# LiDAR_Schematic.net
KiCad netlist of a schematic drawn in Altium Designer
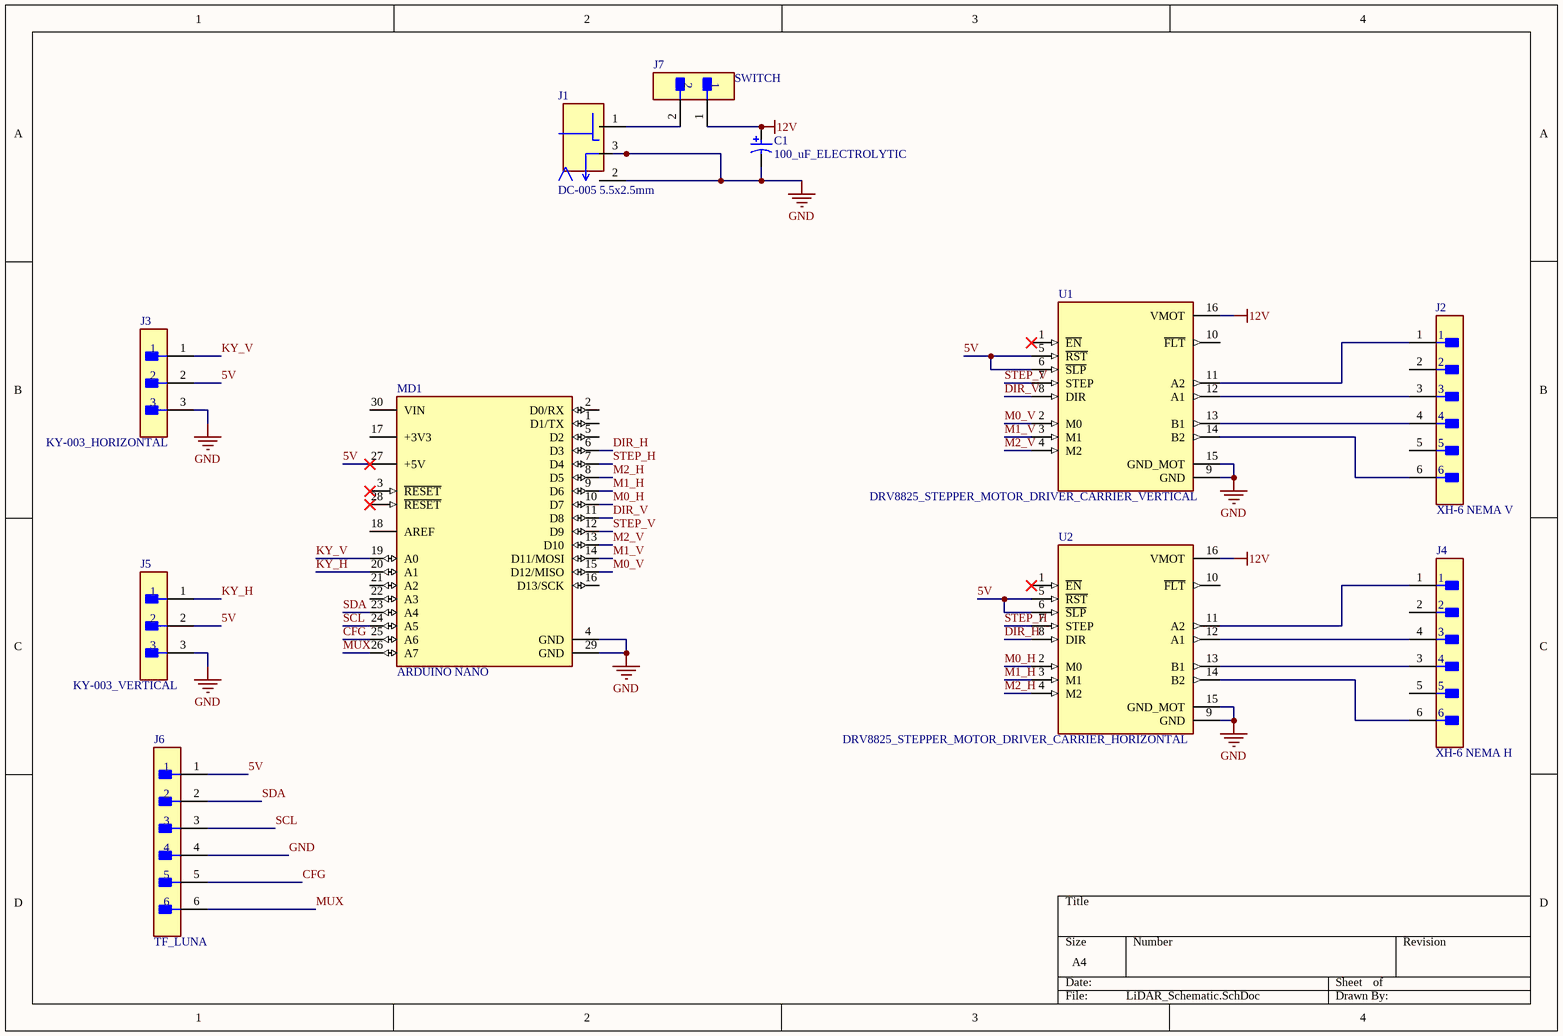
[diagram p0: LiDAR_Schematic.SchDoc]

(export (version "E")
  (design (tool "Eeschema 10.0.6"))
  (components
    (comp (ref "C1")
      (value "100_uF_ELECTROLYTIC")
      (footprint "CAPPR55-250-1120X630X1220")
      (fields (field (name "MANUFACTURER") "Panasonic"))
      (libsource (lib "Altium Content Vault") (part "CAP-P-2"))
    )
    (comp (ref "J1")
      (value "DC-005 5.5x2.5mm")
      (footprint "GCT_DCJ250-10-A-XX-X_REVA")
      (description "Power Barrel Connector Jack 2.55mm ID (0.100), 5.50mm OD (0.217) Through Hole, Right Angle")
      (fields (field (name "MP") "DCJ250-10-A-K1-K") (field (name "MF") "Global Connector Technology"))
      (libsource (lib "DCJ250-10-A-XX-X_REVA") (part "DCJ250-10-A-XX-X_REVA"))
    )
    (comp (ref "J2")
      (value "XH-6 NEMA V")
      (footprint "FP-B6B-XH-A_LF_SN-MFG")
      (description "CONN HEADER VERT 6POS 2.5MM")
      (libsource (lib "") (part "f2cb566baf1c37ab5a3b8e90bbeafd6_1"))
    )
    (comp (ref "J3")
      (value "KY-003_HORIZONTAL")
      (footprint "FP-87224-3-MFG")
      (description "CONN HEADER VERT 3POS 2.54MM")
      (libsource (lib "Altium Content Vault") (part "0d3f023dd272f625e17a2be33dea85f"))
    )
    (comp (ref "J4")
      (value "XH-6 NEMA H")
      (footprint "FP-B6B-XH-A_LF_SN-MFG")
      (description "CONN HEADER VERT 6POS 2.5MM")
      (libsource (lib "Altium Content Vault") (part "f2cb566baf1c37ab5a3b8e90bbeafd6"))
    )
    (comp (ref "J5")
      (value "KY-003_VERTICAL")
      (footprint "FP-87224-3-MFG")
      (description "CONN HEADER VERT 3POS 2.54MM")
      (libsource (lib "Altium Content Vault") (part "0d3f023dd272f625e17a2be33dea85f"))
    )
    (comp (ref "J6")
      (value "TF_LUNA")
      (footprint "FP-22-28-4060-MFG")
      (description "CONN HEADER VERT 6POS 2.54MM")
      (libsource (lib "") (part "f2cb566baf1c37ab5a3b8e90bbeafd6_2"))
    )
    (comp (ref "J7")
      (value "SWITCH")
      (footprint "FP-TSW-102-07-S-S-MFG")
      (description "CONN HEADER VERT 2POS 2.54MM")
      (libsource (lib "Altium Content Vault") (part "3bc925449376181038e59eaffc5286c"))
    )
    (comp (ref "MD1")
      (value "ARDUINO NANO")
      (footprint "FP-A000005-MFG")
      (description "ARDUINO NANO ATMEGA328 EVAL BRD")
      (libsource (lib "Altium Content Vault") (part "d190c066e99afd1c6882cf92e11b2cc"))
    )
    (comp (ref "U1")
      (value "DRV8825_STEPPER_MOTOR_DRIVER_CARRIER_VERTICAL")
      (footprint "IC_DRV8825_STEPPER_MOTOR_DRIVER_CARRIER")
      (description "Stepper motor controler; IC: DRV8825; 1.5A; Uin mot: 8.2Ã·45V")
      (fields (field (name "MP") "DRV8825_STEPPER_MOTOR_DRIVER_CARRIER"))
      (libsource (lib "DRV8825_STEPPER_MOTOR_DRIVER_CARRIER") (part "DRV8825_STEPPER_MOTOR_DRIVER_CARRIER"))
    )
    (comp (ref "U2")
      (value "DRV8825_STEPPER_MOTOR_DRIVER_CARRIER_HORIZONTAL")
      (footprint "IC_DRV8825_STEPPER_MOTOR_DRIVER_CARRIER")
      (description "Stepper motor controler; IC: DRV8825; 1.5A; Uin mot: 8.2Ã·45V")
      (fields (field (name "MP") "DRV8825_STEPPER_MOTOR_DRIVER_CARRIER"))
      (libsource (lib "DRV8825_STEPPER_MOTOR_DRIVER_CARRIER") (part "DRV8825_STEPPER_MOTOR_DRIVER_CARRIER"))
    )
  )
  (nets
    (net (code "1") (name "/5V") (class "Default")
      (node (ref "J3") (pin "2") (pinfunction "2_2") (pintype "passive"))
      (node (ref "J5") (pin "2") (pinfunction "2_2") (pintype "passive"))
      (node (ref "J6") (pin "1") (pinfunction "1_1") (pintype "passive"))
      (node (ref "MD1") (pin "27") (pinfunction "+5V_27") (pintype "power_in"))
      (node (ref "U1") (pin "5") (pinfunction "~{RST}_5") (pintype "input"))
      (node (ref "U1") (pin "6") (pinfunction "~{SLP}_6") (pintype "input"))
      (node (ref "U2") (pin "5") (pinfunction "~{RST}_5") (pintype "input"))
      (node (ref "U2") (pin "6") (pinfunction "~{SLP}_6") (pintype "input"))
    )
    (net (code "2") (name "/CFG") (class "Default")
      (node (ref "J6") (pin "5") (pinfunction "5_5") (pintype "passive"))
      (node (ref "MD1") (pin "25") (pinfunction "A6_25") (pintype "bidirectional"))
    )
    (net (code "3") (name "/DIR_H") (class "Default")
      (node (ref "MD1") (pin "6") (pinfunction "D3_6") (pintype "bidirectional"))
      (node (ref "U2") (pin "8") (pinfunction "DIR_8") (pintype "input"))
    )
    (net (code "4") (name "/DIR_V") (class "Default")
      (node (ref "MD1") (pin "11") (pinfunction "D8_11") (pintype "bidirectional"))
      (node (ref "U1") (pin "8") (pinfunction "DIR_8") (pintype "input"))
    )
    (net (code "5") (name "/KY_H") (class "Default")
      (node (ref "J5") (pin "1") (pinfunction "1_1") (pintype "passive"))
      (node (ref "MD1") (pin "20") (pinfunction "A1_20") (pintype "bidirectional"))
    )
    (net (code "6") (name "/KY_V") (class "Default")
      (node (ref "J3") (pin "1") (pinfunction "1_1") (pintype "passive"))
      (node (ref "MD1") (pin "19") (pinfunction "A0_19") (pintype "bidirectional"))
    )
    (net (code "7") (name "/M0_H") (class "Default")
      (node (ref "MD1") (pin "10") (pinfunction "D7_10") (pintype "bidirectional"))
      (node (ref "U2") (pin "2") (pinfunction "M0_2") (pintype "input"))
    )
    (net (code "8") (name "/M0_V") (class "Default")
      (node (ref "MD1") (pin "15") (pinfunction "D12/MISO_15") (pintype "bidirectional"))
      (node (ref "U1") (pin "2") (pinfunction "M0_2") (pintype "input"))
    )
    (net (code "9") (name "/M1_H") (class "Default")
      (node (ref "MD1") (pin "9") (pinfunction "D6_9") (pintype "bidirectional"))
      (node (ref "U2") (pin "3") (pinfunction "M1_3") (pintype "input"))
    )
    (net (code "10") (name "/M1_V") (class "Default")
      (node (ref "MD1") (pin "14") (pinfunction "D11/MOSI_14") (pintype "bidirectional"))
      (node (ref "U1") (pin "3") (pinfunction "M1_3") (pintype "input"))
    )
    (net (code "11") (name "/M2_H") (class "Default")
      (node (ref "MD1") (pin "8") (pinfunction "D5_8") (pintype "bidirectional"))
      (node (ref "U2") (pin "4") (pinfunction "M2_4") (pintype "input"))
    )
    (net (code "12") (name "/M2_V") (class "Default")
      (node (ref "MD1") (pin "13") (pinfunction "D10_13") (pintype "bidirectional"))
      (node (ref "U1") (pin "4") (pinfunction "M2_4") (pintype "input"))
    )
    (net (code "13") (name "/MUX") (class "Default")
      (node (ref "J6") (pin "6") (pinfunction "6_6") (pintype "passive"))
      (node (ref "MD1") (pin "26") (pinfunction "A7_26") (pintype "bidirectional"))
    )
    (net (code "14") (name "/SCL") (class "Default")
      (node (ref "J6") (pin "3") (pinfunction "3_3") (pintype "passive"))
      (node (ref "MD1") (pin "24") (pinfunction "A5_24") (pintype "bidirectional"))
    )
    (net (code "15") (name "/SDA") (class "Default")
      (node (ref "J6") (pin "2") (pinfunction "2_2") (pintype "passive"))
      (node (ref "MD1") (pin "23") (pinfunction "A4_23") (pintype "bidirectional"))
    )
    (net (code "16") (name "/STEP_H") (class "Default")
      (node (ref "MD1") (pin "7") (pinfunction "D4_7") (pintype "bidirectional"))
      (node (ref "U2") (pin "7") (pinfunction "STEP_7") (pintype "input"))
    )
    (net (code "17") (name "/STEP_V") (class "Default")
      (node (ref "MD1") (pin "12") (pinfunction "D9_12") (pintype "bidirectional"))
      (node (ref "U1") (pin "7") (pinfunction "STEP_7") (pintype "input"))
    )
    (net (code "18") (name "12V") (class "Default")
      (node (ref "C1") (pin "1") (pinfunction "1_1") (pintype "passive"))
      (node (ref "J7") (pin "1") (pinfunction "1_1") (pintype "passive"))
      (node (ref "U1") (pin "16") (pinfunction "VMOT_16") (pintype "power_in"))
      (node (ref "U2") (pin "16") (pinfunction "VMOT_16") (pintype "power_in"))
    )
    (net (code "19") (name "GND") (class "Default")
      (node (ref "C1") (pin "2") (pinfunction "2_2") (pintype "passive"))
      (node (ref "J1") (pin "2") (pinfunction "TIP_2") (pintype "passive"))
      (node (ref "J1") (pin "3") (pinfunction "SHUNT_3") (pintype "passive"))
      (node (ref "J3") (pin "3") (pinfunction "3_3") (pintype "passive"))
      (node (ref "J5") (pin "3") (pinfunction "3_3") (pintype "passive"))
      (node (ref "J6") (pin "4") (pinfunction "4_4") (pintype "passive"))
      (node (ref "MD1") (pin "29") (pinfunction "GND_29") (pintype "power_in"))
      (node (ref "MD1") (pin "4") (pinfunction "GND_4") (pintype "power_in"))
      (node (ref "U1") (pin "15") (pinfunction "GND_MOT_15") (pintype "power_in"))
      (node (ref "U1") (pin "9") (pinfunction "GND_9") (pintype "power_in"))
      (node (ref "U2") (pin "15") (pinfunction "GND_MOT_15") (pintype "power_in"))
      (node (ref "U2") (pin "9") (pinfunction "GND_9") (pintype "power_in"))
    )
    (net (code "20") (name "Net-(J1-CENTER)") (class "Default")
      (node (ref "J1") (pin "1") (pinfunction "CENTER_1") (pintype "passive"))
      (node (ref "J7") (pin "2") (pinfunction "2_2") (pintype "passive"))
    )
    (net (code "21") (name "Net-(U1-A1)") (class "Default")
      (node (ref "J2") (pin "3") (pinfunction "3_3") (pintype "passive"))
      (node (ref "U1") (pin "12") (pinfunction "A1_12") (pintype "output"))
    )
    (net (code "22") (name "Net-(U1-A2)") (class "Default")
      (node (ref "J2") (pin "1") (pinfunction "1_1") (pintype "passive"))
      (node (ref "U1") (pin "11") (pinfunction "A2_11") (pintype "output"))
    )
    (net (code "23") (name "Net-(U1-B1)") (class "Default")
      (node (ref "J2") (pin "4") (pinfunction "4_4") (pintype "passive"))
      (node (ref "U1") (pin "13") (pinfunction "B1_13") (pintype "output"))
    )
    (net (code "24") (name "Net-(U1-B2)") (class "Default")
      (node (ref "J2") (pin "6") (pinfunction "6_6") (pintype "passive"))
      (node (ref "U1") (pin "14") (pinfunction "B2_14") (pintype "output"))
    )
    (net (code "25") (name "Net-(U2-A1)") (class "Default")
      (node (ref "J4") (pin "4") (pinfunction "4_4") (pintype "passive"))
      (node (ref "U2") (pin "12") (pinfunction "A1_12") (pintype "output"))
    )
    (net (code "26") (name "Net-(U2-A2)") (class "Default")
      (node (ref "J4") (pin "1") (pinfunction "1_1") (pintype "passive"))
      (node (ref "U2") (pin "11") (pinfunction "A2_11") (pintype "output"))
    )
    (net (code "27") (name "Net-(U2-B1)") (class "Default")
      (node (ref "J4") (pin "3") (pinfunction "3_3") (pintype "passive"))
      (node (ref "U2") (pin "13") (pinfunction "B1_13") (pintype "output"))
    )
    (net (code "28") (name "Net-(U2-B2)") (class "Default")
      (node (ref "J4") (pin "6") (pinfunction "6_6") (pintype "passive"))
      (node (ref "U2") (pin "14") (pinfunction "B2_14") (pintype "output"))
    )
    (net (code "29") (name "unconnected-(J2-Pad2)") (class "Default")
      (node (ref "J2") (pin "2") (pinfunction "2_2") (pintype "passive"))
    )
    (net (code "30") (name "unconnected-(J2-Pad5)") (class "Default")
      (node (ref "J2") (pin "5") (pinfunction "5_5") (pintype "passive"))
    )
    (net (code "31") (name "unconnected-(J4-Pad2)") (class "Default")
      (node (ref "J4") (pin "2") (pinfunction "2_2") (pintype "passive"))
    )
    (net (code "32") (name "unconnected-(J4-Pad5)") (class "Default")
      (node (ref "J4") (pin "5") (pinfunction "5_5") (pintype "passive"))
    )
    (net (code "33") (name "unconnected-(MD1-+3V3-Pad17)") (class "Default")
      (node (ref "MD1") (pin "17") (pinfunction "+3V3_17") (pintype "power_in"))
    )
    (net (code "34") (name "unconnected-(MD1-A2-Pad21)") (class "Default")
      (node (ref "MD1") (pin "21") (pinfunction "A2_21") (pintype "bidirectional"))
    )
    (net (code "35") (name "unconnected-(MD1-A3-Pad22)") (class "Default")
      (node (ref "MD1") (pin "22") (pinfunction "A3_22") (pintype "bidirectional"))
    )
    (net (code "36") (name "unconnected-(MD1-AREF-Pad18)") (class "Default")
      (node (ref "MD1") (pin "18") (pinfunction "AREF_18") (pintype "passive"))
    )
    (net (code "37") (name "unconnected-(MD1-D0{slash}RX-Pad2)") (class "Default")
      (node (ref "MD1") (pin "2") (pinfunction "D0/RX_2") (pintype "bidirectional"))
    )
    (net (code "38") (name "unconnected-(MD1-D1{slash}TX-Pad1)") (class "Default")
      (node (ref "MD1") (pin "1") (pinfunction "D1/TX_1") (pintype "bidirectional"))
    )
    (net (code "39") (name "unconnected-(MD1-D2-Pad5)") (class "Default")
      (node (ref "MD1") (pin "5") (pinfunction "D2_5") (pintype "bidirectional"))
    )
    (net (code "40") (name "unconnected-(MD1-D13{slash}SCK-Pad16)") (class "Default")
      (node (ref "MD1") (pin "16") (pinfunction "D13/SCK_16") (pintype "bidirectional"))
    )
    (net (code "41") (name "unconnected-(MD1-VIN-Pad30)") (class "Default")
      (node (ref "MD1") (pin "30") (pinfunction "VIN_30") (pintype "power_in"))
    )
    (net (code "42") (name "unconnected-(MD1-~{RESET}-Pad3)") (class "Default")
      (node (ref "MD1") (pin "3") (pinfunction "~{RESET}_3") (pintype "input+no_connect"))
    )
    (net (code "43") (name "unconnected-(MD1-~{RESET}-Pad28)") (class "Default")
      (node (ref "MD1") (pin "28") (pinfunction "~{RESET}_28") (pintype "input+no_connect"))
    )
    (net (code "44") (name "unconnected-(U1-~{EN}-Pad1)") (class "Default")
      (node (ref "U1") (pin "1") (pinfunction "~{EN}_1") (pintype "input+no_connect"))
    )
    (net (code "45") (name "unconnected-(U1-~{FLT}-Pad10)") (class "Default")
      (node (ref "U1") (pin "10") (pinfunction "~{FLT}_10") (pintype "output"))
    )
    (net (code "46") (name "unconnected-(U2-~{EN}-Pad1)") (class "Default")
      (node (ref "U2") (pin "1") (pinfunction "~{EN}_1") (pintype "input+no_connect"))
    )
    (net (code "47") (name "unconnected-(U2-~{FLT}-Pad10)") (class "Default")
      (node (ref "U2") (pin "10") (pinfunction "~{FLT}_10") (pintype "output"))
    )
  )
)
